# motor.net
KiCad netlist of a schematic drawn in Altium Designer
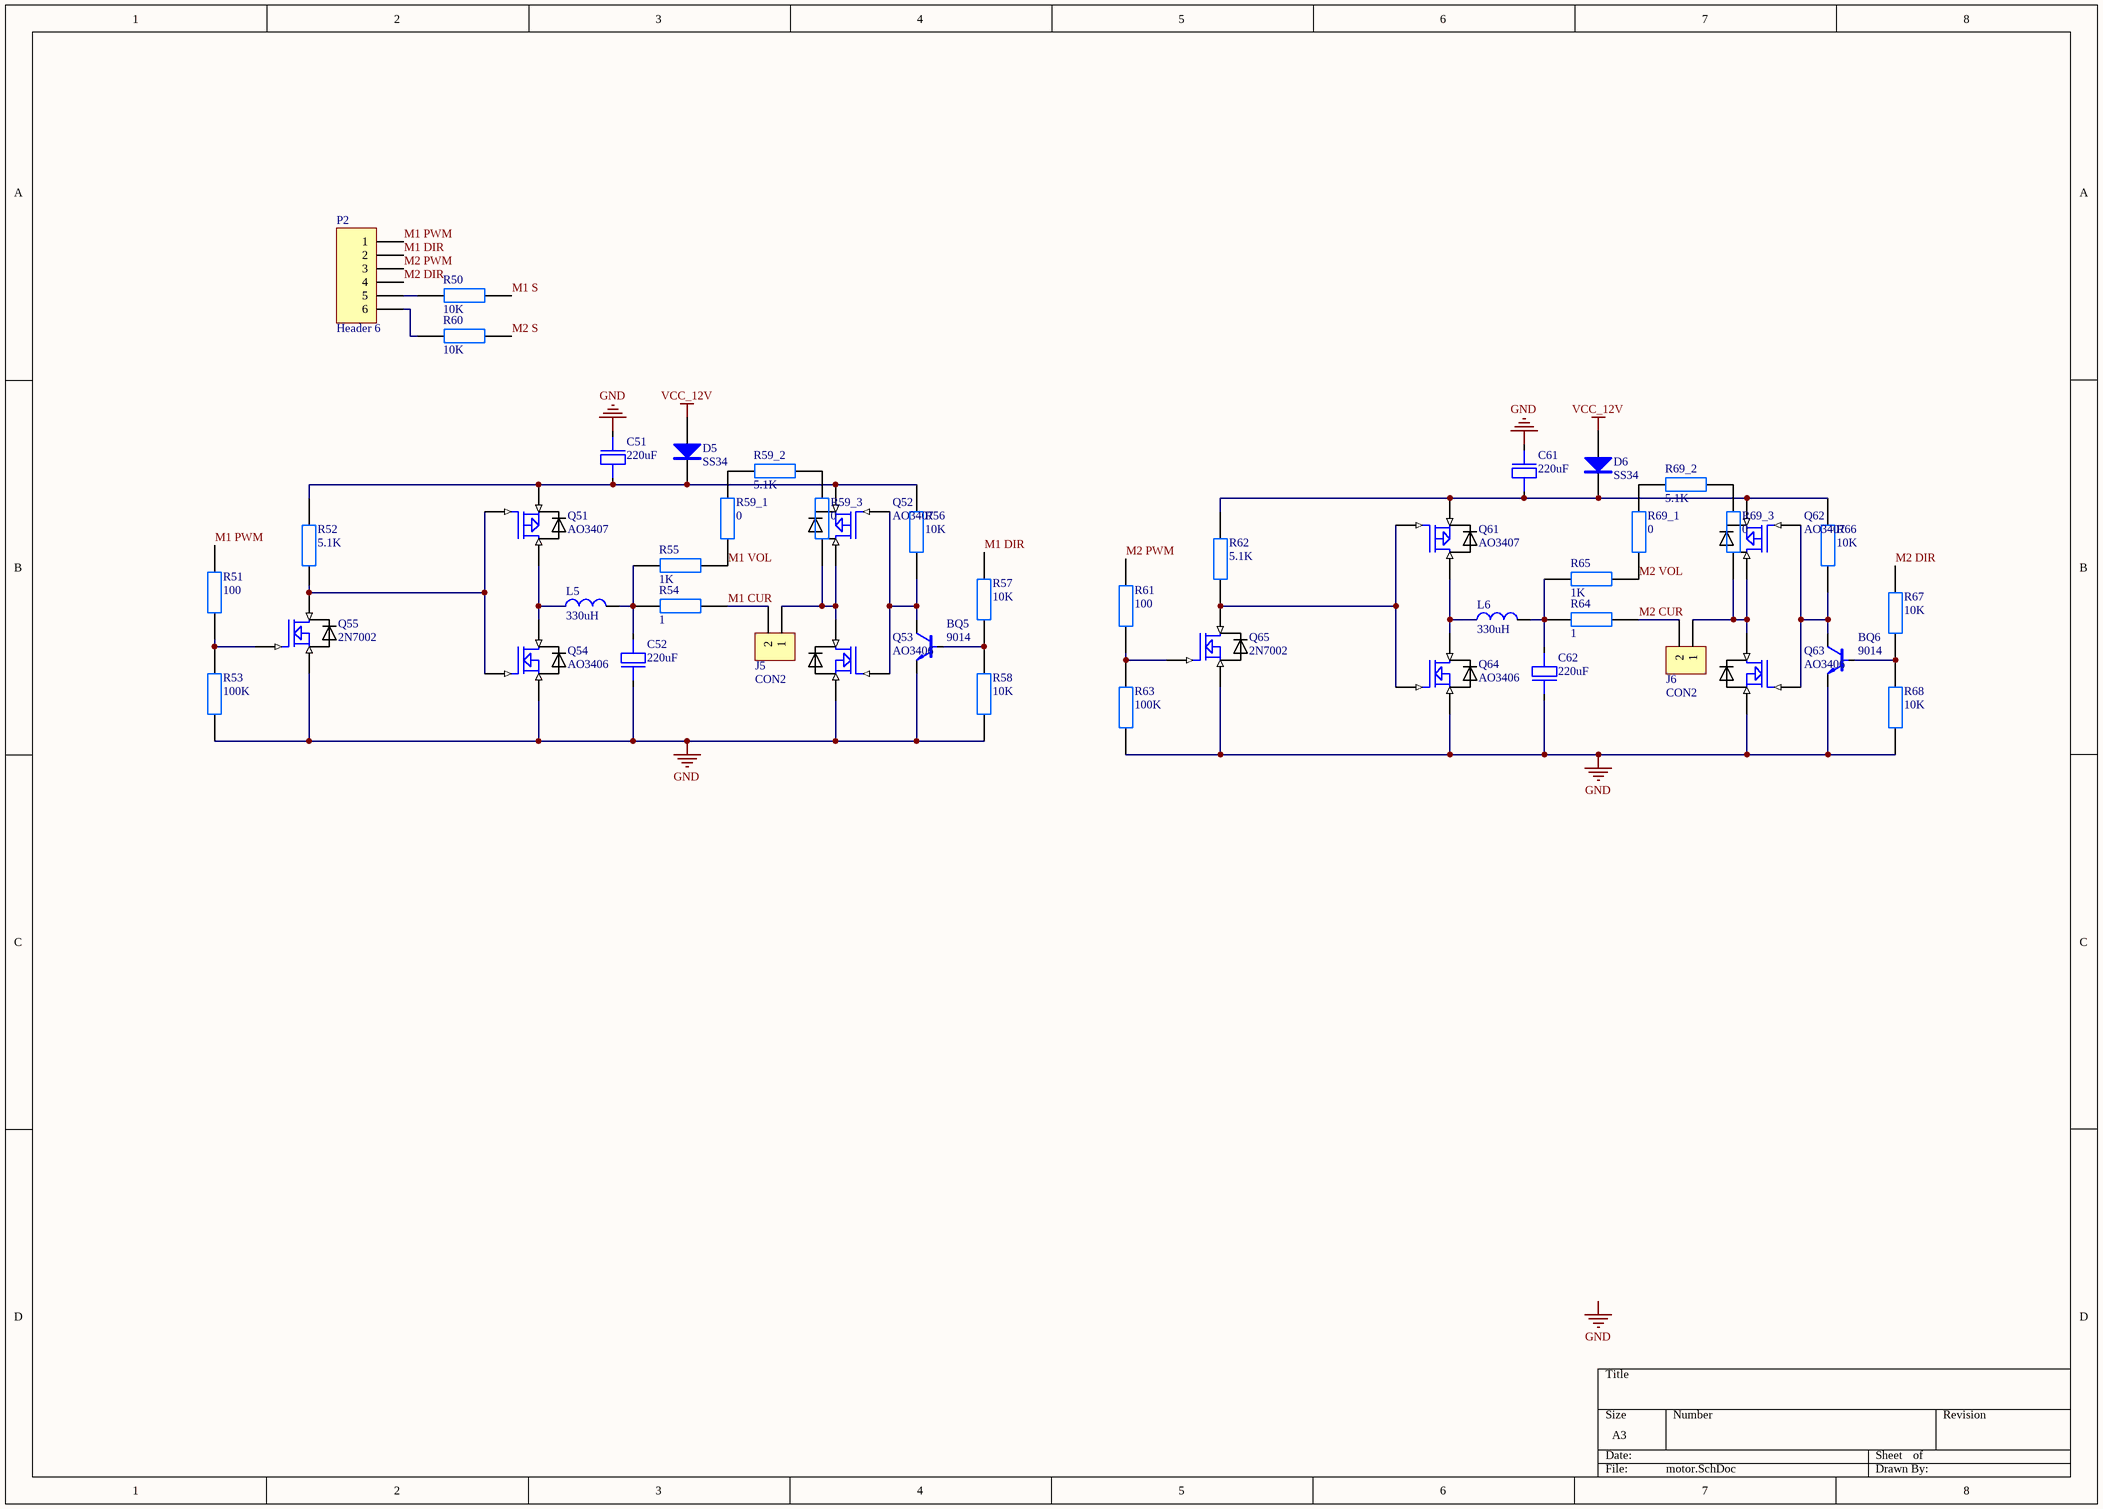
[diagram p0: motor.SchDoc]

(export (version "E")
  (design (tool "Eeschema 10.0.6"))
  (components
    (comp (ref "BQ5")
      (value "9014")
      (footprint "SOT-23")
      (description "transistor")
      (libsource (lib "common") (part "9014"))
    )
    (comp (ref "BQ6")
      (value "9014")
      (footprint "SOT-23")
      (description "transistor")
      (libsource (lib "common") (part "9014"))
    )
    (comp (ref "C51")
      (value "220uF")
      (footprint "SMD-EC-F10")
      (libsource (lib "common") (part "Electrolytic CAP"))
    )
    (comp (ref "C52")
      (value "220uF")
      (footprint "SMD-EC-F10")
      (libsource (lib "common") (part "Electrolytic CAP"))
    )
    (comp (ref "C61")
      (value "220uF")
      (footprint "SMD-EC-F10")
      (libsource (lib "common") (part "Electrolytic CAP"))
    )
    (comp (ref "C62")
      (value "220uF")
      (footprint "SMD-EC-F10")
      (libsource (lib "common") (part "Electrolytic CAP"))
    )
    (comp (ref "D5")
      (value "SS34")
      (footprint "SMA")
      (description "Diode")
      (libsource (lib "common") (part "SS14"))
    )
    (comp (ref "D6")
      (value "SS34")
      (footprint "SMA")
      (description "Diode")
      (libsource (lib "common") (part "SS14"))
    )
    (comp (ref "J5") (value "CON2") (footprint "con2") (libsource (lib "common") (part "CON2")))
    (comp (ref "J6") (value "CON2") (footprint "con2") (libsource (lib "common") (part "CON2")))
    (comp (ref "L5") (value "330uH") (footprint "12x12") (libsource (lib "common") (part "Inductance")))
    (comp (ref "L6") (value "330uH") (footprint "12x12") (libsource (lib "common") (part "Inductance")))
    (comp (ref "P2")
      (value "Header 6")
      (footprint "HDR1X6")
      (description "Header, 6-Pin")
      (fields (field (name "PUBLISHER") "Altium Limited"))
      (libsource (lib "Miscellaneous Connectors") (part "Header 6"))
    )
    (comp (ref "Q51") (value "AO3407") (footprint "sot-23") (libsource (lib "common") (part "AO3407")))
    (comp (ref "Q52") (value "AO3407") (footprint "sot-23") (libsource (lib "common") (part "AO3407")))
    (comp (ref "Q53") (value "AO3406") (footprint "sot-23") (libsource (lib "common") (part "AO3406")))
    (comp (ref "Q54") (value "AO3406") (footprint "sot-23") (libsource (lib "common") (part "AO3406")))
    (comp (ref "Q55") (value "2N7002") (footprint "sot-23") (libsource (lib "common") (part "2N7002")))
    (comp (ref "Q61") (value "AO3407") (footprint "sot-23") (libsource (lib "common") (part "AO3407")))
    (comp (ref "Q62") (value "AO3407") (footprint "sot-23") (libsource (lib "common") (part "AO3407")))
    (comp (ref "Q63") (value "AO3406") (footprint "sot-23") (libsource (lib "common") (part "AO3406")))
    (comp (ref "Q64") (value "AO3406") (footprint "sot-23") (libsource (lib "common") (part "AO3406")))
    (comp (ref "Q65") (value "2N7002") (footprint "sot-23") (libsource (lib "common") (part "2N7002")))
    (comp (ref "R50")
      (value "10K")
      (footprint "0805")
      (description "RES")
      (libsource (lib "common") (part "RES"))
    )
    (comp (ref "R51")
      (value "100")
      (footprint "0805")
      (description "RES")
      (libsource (lib "common") (part "RES"))
    )
    (comp (ref "R52")
      (value "5.1K")
      (footprint "0805")
      (description "RES")
      (libsource (lib "common") (part "RES"))
    )
    (comp (ref "R53")
      (value "100K")
      (footprint "0805")
      (description "RES")
      (libsource (lib "common") (part "RES"))
    )
    (comp (ref "R54")
      (value "1")
      (footprint "2512")
      (description "RES")
      (libsource (lib "common") (part "RES"))
    )
    (comp (ref "R55")
      (value "1K")
      (footprint "0805")
      (description "RES")
      (libsource (lib "common") (part "RES"))
    )
    (comp (ref "R56")
      (value "10K")
      (footprint "0805")
      (description "RES")
      (libsource (lib "common") (part "RES"))
    )
    (comp (ref "R57")
      (value "10K")
      (footprint "0805")
      (description "RES")
      (libsource (lib "common") (part "RES"))
    )
    (comp (ref "R58")
      (value "10K")
      (footprint "0805")
      (description "RES")
      (libsource (lib "common") (part "RES"))
    )
    (comp (ref "R59_1")
      (value "0")
      (footprint "0805")
      (description "RES")
      (libsource (lib "common") (part "RES"))
    )
    (comp (ref "R59_2")
      (value "5.1K")
      (footprint "0805")
      (description "RES")
      (libsource (lib "common") (part "RES"))
    )
    (comp (ref "R59_3")
      (value "0")
      (footprint "0805")
      (description "RES")
      (libsource (lib "common") (part "RES"))
    )
    (comp (ref "R60")
      (value "10K")
      (footprint "0805")
      (description "RES")
      (libsource (lib "common") (part "RES"))
    )
    (comp (ref "R61")
      (value "100")
      (footprint "0805")
      (description "RES")
      (libsource (lib "common") (part "RES"))
    )
    (comp (ref "R62")
      (value "5.1K")
      (footprint "0805")
      (description "RES")
      (libsource (lib "common") (part "RES"))
    )
    (comp (ref "R63")
      (value "100K")
      (footprint "0805")
      (description "RES")
      (libsource (lib "common") (part "RES"))
    )
    (comp (ref "R64")
      (value "1")
      (footprint "2512")
      (description "RES")
      (libsource (lib "common") (part "RES"))
    )
    (comp (ref "R65")
      (value "1K")
      (footprint "0805")
      (description "RES")
      (libsource (lib "common") (part "RES"))
    )
    (comp (ref "R66")
      (value "10K")
      (footprint "0805")
      (description "RES")
      (libsource (lib "common") (part "RES"))
    )
    (comp (ref "R67")
      (value "10K")
      (footprint "0805")
      (description "RES")
      (libsource (lib "common") (part "RES"))
    )
    (comp (ref "R68")
      (value "10K")
      (footprint "0805")
      (description "RES")
      (libsource (lib "common") (part "RES"))
    )
    (comp (ref "R69_1")
      (value "0")
      (footprint "0805")
      (description "RES")
      (libsource (lib "common") (part "RES"))
    )
    (comp (ref "R69_2")
      (value "5.1K")
      (footprint "0805")
      (description "RES")
      (libsource (lib "common") (part "RES"))
    )
    (comp (ref "R69_3")
      (value "0")
      (footprint "0805")
      (description "RES")
      (libsource (lib "common") (part "RES"))
    )
  )
  (nets
    (net (code "1") (name "/M1 CUR") (class "Default")
      (node (ref "J5") (pin "2") (pinfunction "2_2") (pintype "passive"))
      (node (ref "R54") (pin "2") (pinfunction "2_2") (pintype "passive"))
    )
    (net (code "2") (name "/M1 DIR") (class "Default")
      (node (ref "P2") (pin "2") (pinfunction "2_2") (pintype "passive"))
      (node (ref "R57") (pin "2") (pinfunction "2_2") (pintype "passive"))
    )
    (net (code "3") (name "/M1 PWM") (class "Default")
      (node (ref "P2") (pin "1") (pinfunction "1_1") (pintype "passive"))
      (node (ref "R51") (pin "2") (pinfunction "2_2") (pintype "passive"))
    )
    (net (code "4") (name "/M1 S") (class "Default")
      (node (ref "R50") (pin "1") (pinfunction "1_1") (pintype "passive"))
    )
    (net (code "5") (name "/M1 VOL") (class "Default")
      (node (ref "R55") (pin "2") (pinfunction "2_2") (pintype "passive"))
      (node (ref "R59_1") (pin "1") (pinfunction "1_1") (pintype "passive"))
    )
    (net (code "6") (name "/M2 CUR") (class "Default")
      (node (ref "J6") (pin "2") (pinfunction "2_2") (pintype "passive"))
      (node (ref "R64") (pin "2") (pinfunction "2_2") (pintype "passive"))
    )
    (net (code "7") (name "/M2 DIR") (class "Default")
      (node (ref "P2") (pin "4") (pinfunction "4_4") (pintype "passive"))
      (node (ref "R67") (pin "2") (pinfunction "2_2") (pintype "passive"))
    )
    (net (code "8") (name "/M2 PWM") (class "Default")
      (node (ref "P2") (pin "3") (pinfunction "3_3") (pintype "passive"))
      (node (ref "R61") (pin "2") (pinfunction "2_2") (pintype "passive"))
    )
    (net (code "9") (name "/M2 S") (class "Default")
      (node (ref "R60") (pin "1") (pinfunction "1_1") (pintype "passive"))
    )
    (net (code "10") (name "/M2 VOL") (class "Default")
      (node (ref "R65") (pin "2") (pinfunction "2_2") (pintype "passive"))
      (node (ref "R69_1") (pin "1") (pinfunction "1_1") (pintype "passive"))
    )
    (net (code "11") (name "GND") (class "Default")
      (node (ref "BQ5") (pin "e") (pinfunction "e_e") (pintype "passive"))
      (node (ref "BQ6") (pin "e") (pinfunction "e_e") (pintype "passive"))
      (node (ref "C51") (pin "2") (pinfunction "2_2") (pintype "passive"))
      (node (ref "C52") (pin "2") (pinfunction "2_2") (pintype "passive"))
      (node (ref "C61") (pin "2") (pinfunction "2_2") (pintype "passive"))
      (node (ref "C62") (pin "2") (pinfunction "2_2") (pintype "passive"))
      (node (ref "Q53") (pin "3") (pinfunction "S_3") (pintype "input"))
      (node (ref "Q54") (pin "3") (pinfunction "S_3") (pintype "input"))
      (node (ref "Q55") (pin "3") (pinfunction "S_3") (pintype "input"))
      (node (ref "Q63") (pin "3") (pinfunction "S_3") (pintype "input"))
      (node (ref "Q64") (pin "3") (pinfunction "S_3") (pintype "input"))
      (node (ref "Q65") (pin "3") (pinfunction "S_3") (pintype "input"))
      (node (ref "R53") (pin "1") (pinfunction "1_1") (pintype "passive"))
      (node (ref "R58") (pin "1") (pinfunction "1_1") (pintype "passive"))
      (node (ref "R63") (pin "1") (pinfunction "1_1") (pintype "passive"))
      (node (ref "R68") (pin "1") (pinfunction "1_1") (pintype "passive"))
    )
    (net (code "12") (name "Net-(BQ5-Padb)") (class "Default")
      (node (ref "BQ5") (pin "b") (pinfunction "b_b") (pintype "passive"))
      (node (ref "R57") (pin "1") (pinfunction "1_1") (pintype "passive"))
      (node (ref "R58") (pin "2") (pinfunction "2_2") (pintype "passive"))
    )
    (net (code "13") (name "Net-(BQ6-Padb)") (class "Default")
      (node (ref "BQ6") (pin "b") (pinfunction "b_b") (pintype "passive"))
      (node (ref "R67") (pin "1") (pinfunction "1_1") (pintype "passive"))
      (node (ref "R68") (pin "2") (pinfunction "2_2") (pintype "passive"))
    )
    (net (code "14") (name "Net-(C52-Pad1)") (class "Default")
      (node (ref "C52") (pin "1") (pinfunction "1_1") (pintype "passive"))
      (node (ref "L5") (pin "1") (pinfunction "1_1") (pintype "passive"))
      (node (ref "R54") (pin "1") (pinfunction "1_1") (pintype "passive"))
      (node (ref "R55") (pin "1") (pinfunction "1_1") (pintype "passive"))
    )
    (net (code "15") (name "Net-(C62-Pad1)") (class "Default")
      (node (ref "C62") (pin "1") (pinfunction "1_1") (pintype "passive"))
      (node (ref "L6") (pin "1") (pinfunction "1_1") (pintype "passive"))
      (node (ref "R64") (pin "1") (pinfunction "1_1") (pintype "passive"))
      (node (ref "R65") (pin "1") (pinfunction "1_1") (pintype "passive"))
    )
    (net (code "16") (name "Net-(D5-K)") (class "Default")
      (node (ref "C51") (pin "1") (pinfunction "1_1") (pintype "passive"))
      (node (ref "D5") (pin "2") (pinfunction "K_2") (pintype "passive"))
      (node (ref "Q51") (pin "3") (pinfunction "S_3") (pintype "input"))
      (node (ref "Q52") (pin "3") (pinfunction "S_3") (pintype "input"))
      (node (ref "R52") (pin "2") (pinfunction "2_2") (pintype "passive"))
      (node (ref "R56") (pin "2") (pinfunction "2_2") (pintype "passive"))
    )
    (net (code "17") (name "Net-(D6-K)") (class "Default")
      (node (ref "C61") (pin "1") (pinfunction "1_1") (pintype "passive"))
      (node (ref "D6") (pin "2") (pinfunction "K_2") (pintype "passive"))
      (node (ref "Q61") (pin "3") (pinfunction "S_3") (pintype "input"))
      (node (ref "Q62") (pin "3") (pinfunction "S_3") (pintype "input"))
      (node (ref "R62") (pin "2") (pinfunction "2_2") (pintype "passive"))
      (node (ref "R66") (pin "2") (pinfunction "2_2") (pintype "passive"))
    )
    (net (code "18") (name "Net-(P2-Pad5)") (class "Default")
      (node (ref "P2") (pin "5") (pinfunction "5_5") (pintype "passive"))
      (node (ref "R50") (pin "2") (pinfunction "2_2") (pintype "passive"))
    )
    (net (code "19") (name "Net-(P2-Pad6)") (class "Default")
      (node (ref "P2") (pin "6") (pinfunction "6_6") (pintype "passive"))
      (node (ref "R60") (pin "2") (pinfunction "2_2") (pintype "passive"))
    )
    (net (code "20") (name "Net-(Q51-D)") (class "Default")
      (node (ref "L5") (pin "2") (pinfunction "2_2") (pintype "passive"))
      (node (ref "Q51") (pin "2") (pinfunction "D_2") (pintype "input"))
      (node (ref "Q54") (pin "2") (pinfunction "D_2") (pintype "input"))
    )
    (net (code "21") (name "Net-(Q51-G)") (class "Default")
      (node (ref "Q51") (pin "1") (pinfunction "G_1") (pintype "input"))
      (node (ref "Q54") (pin "1") (pinfunction "G_1") (pintype "input"))
      (node (ref "Q55") (pin "2") (pinfunction "D_2") (pintype "input"))
      (node (ref "R52") (pin "1") (pinfunction "1_1") (pintype "passive"))
    )
    (net (code "22") (name "Net-(Q52-D)") (class "Default")
      (node (ref "J5") (pin "1") (pinfunction "1_1") (pintype "passive"))
      (node (ref "Q52") (pin "2") (pinfunction "D_2") (pintype "input"))
      (node (ref "Q53") (pin "2") (pinfunction "D_2") (pintype "input"))
      (node (ref "R59_3") (pin "1") (pinfunction "1_1") (pintype "passive"))
    )
    (net (code "23") (name "Net-(Q52-G)") (class "Default")
      (node (ref "BQ5") (pin "c") (pinfunction "c_c") (pintype "passive"))
      (node (ref "Q52") (pin "1") (pinfunction "G_1") (pintype "input"))
      (node (ref "Q53") (pin "1") (pinfunction "G_1") (pintype "input"))
      (node (ref "R56") (pin "1") (pinfunction "1_1") (pintype "passive"))
    )
    (net (code "24") (name "Net-(Q55-G)") (class "Default")
      (node (ref "Q55") (pin "1") (pinfunction "G_1") (pintype "input"))
      (node (ref "R51") (pin "1") (pinfunction "1_1") (pintype "passive"))
      (node (ref "R53") (pin "2") (pinfunction "2_2") (pintype "passive"))
    )
    (net (code "25") (name "Net-(Q61-D)") (class "Default")
      (node (ref "L6") (pin "2") (pinfunction "2_2") (pintype "passive"))
      (node (ref "Q61") (pin "2") (pinfunction "D_2") (pintype "input"))
      (node (ref "Q64") (pin "2") (pinfunction "D_2") (pintype "input"))
    )
    (net (code "26") (name "Net-(Q61-G)") (class "Default")
      (node (ref "Q61") (pin "1") (pinfunction "G_1") (pintype "input"))
      (node (ref "Q64") (pin "1") (pinfunction "G_1") (pintype "input"))
      (node (ref "Q65") (pin "2") (pinfunction "D_2") (pintype "input"))
      (node (ref "R62") (pin "1") (pinfunction "1_1") (pintype "passive"))
    )
    (net (code "27") (name "Net-(Q62-D)") (class "Default")
      (node (ref "J6") (pin "1") (pinfunction "1_1") (pintype "passive"))
      (node (ref "Q62") (pin "2") (pinfunction "D_2") (pintype "input"))
      (node (ref "Q63") (pin "2") (pinfunction "D_2") (pintype "input"))
      (node (ref "R69_3") (pin "1") (pinfunction "1_1") (pintype "passive"))
    )
    (net (code "28") (name "Net-(Q62-G)") (class "Default")
      (node (ref "BQ6") (pin "c") (pinfunction "c_c") (pintype "passive"))
      (node (ref "Q62") (pin "1") (pinfunction "G_1") (pintype "input"))
      (node (ref "Q63") (pin "1") (pinfunction "G_1") (pintype "input"))
      (node (ref "R66") (pin "1") (pinfunction "1_1") (pintype "passive"))
    )
    (net (code "29") (name "Net-(Q65-G)") (class "Default")
      (node (ref "Q65") (pin "1") (pinfunction "G_1") (pintype "input"))
      (node (ref "R61") (pin "1") (pinfunction "1_1") (pintype "passive"))
      (node (ref "R63") (pin "2") (pinfunction "2_2") (pintype "passive"))
    )
    (net (code "30") (name "Net-(R59_1-Pad2)") (class "Default")
      (node (ref "R59_1") (pin "2") (pinfunction "2_2") (pintype "passive"))
      (node (ref "R59_2") (pin "1") (pinfunction "1_1") (pintype "passive"))
    )
    (net (code "31") (name "Net-(R59_2-Pad2)") (class "Default")
      (node (ref "R59_2") (pin "2") (pinfunction "2_2") (pintype "passive"))
      (node (ref "R59_3") (pin "2") (pinfunction "2_2") (pintype "passive"))
    )
    (net (code "32") (name "Net-(R69_1-Pad2)") (class "Default")
      (node (ref "R69_1") (pin "2") (pinfunction "2_2") (pintype "passive"))
      (node (ref "R69_2") (pin "1") (pinfunction "1_1") (pintype "passive"))
    )
    (net (code "33") (name "Net-(R69_2-Pad2)") (class "Default")
      (node (ref "R69_2") (pin "2") (pinfunction "2_2") (pintype "passive"))
      (node (ref "R69_3") (pin "2") (pinfunction "2_2") (pintype "passive"))
    )
    (net (code "34") (name "VCC_12V") (class "Default")
      (node (ref "D5") (pin "1") (pinfunction "A_1") (pintype "passive"))
      (node (ref "D6") (pin "1") (pinfunction "A_1") (pintype "passive"))
    )
  )
)
